# Sheet1_final.net
KiCad netlist of a schematic drawn in Altium Designer
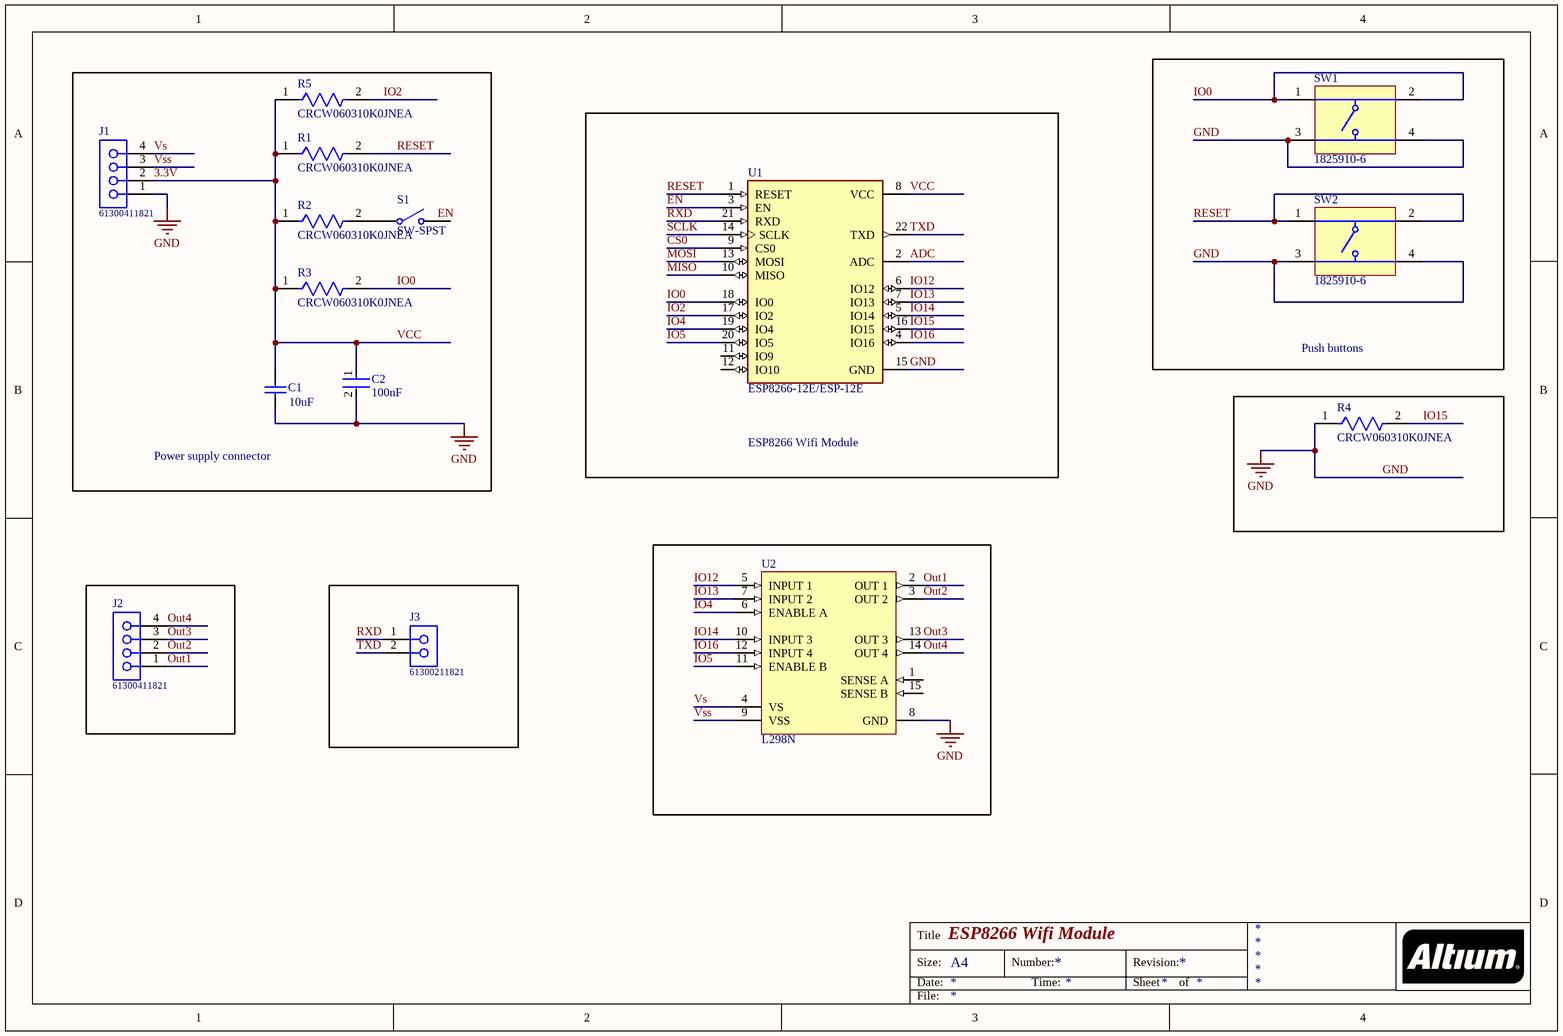
[diagram p0: Sheet1(final).SchDoc]

(export (version "E")
  (design (tool "Eeschema 10.0.6"))
  (components
    (comp (ref "C1")
      (value "10uF")
      (footprint "CAPC2013X95X45ML10T25")
      (fields (field (name "MANUFACTURER") "Murata") (field (name "PART NUMBER") "GRM219R61E106KA12D"))
      (libsource (lib "Altium Content Vault") (part "CAP"))
    )
    (comp (ref "C2")
      (value "100nF")
      (footprint "FP-CL43-IPC_B")
      (description "Cap Ceramic 100nF 500V X7R ±10% SMD 1812 +125°C Embossed T/R")
      (fields (field (name "VOLTAGE") "500V") (field (name "TOLERANCE") "10%"))
      (libsource (lib "Altium Content Vault") (part "b4654b650e69147ec39a6b967a45e02"))
    )
    (comp (ref "J1")
      (value "61300411821")
      (footprint "61300411821")
      (description "WR-PHD Socket Header, THT, pitch 2.54mm, Single Row, Vertical, 4p")
      (fields (field (name "MANUFACTURER") "Wurth Elektronik"))
      (libsource (lib "Altium_WR-PHD (rev20a) (3)") (part "61300411821"))
    )
    (comp (ref "J2")
      (value "61300411821")
      (footprint "61300411821")
      (description "WR-PHD Socket Header, THT, pitch 2.54mm, Single Row, Vertical, 4p")
      (fields (field (name "MANUFACTURER") "Wurth Elektronik"))
      (libsource (lib "Altium_WR-PHD (rev20a) (3)") (part "61300411821"))
    )
    (comp (ref "J3")
      (value "61300211821")
      (footprint "61300211821")
      (description "WR-PHD Socket Header, THT, pitch 2.54mm, Single Row, Vertical, 2p")
      (fields (field (name "MANUFACTURER") "Wurth Elektronik"))
      (libsource (lib "Altium_WR-PHD (rev20a) (3)") (part "61300211821"))
    )
    (comp (ref "R1")
      (value "CRCW060310K0JNEA")
      (footprint "FP-CRCW0603-e3-MFG")
      (description "RES Thick Film, 10kΩ, 5%, 0.1W, 200ppm/°C, 0603")
      (fields (field (name "TOLERANCE") "5%"))
      (libsource (lib "Altium Content Vault") (part "1029c3af85768c4190bb7ad29bc67b5"))
    )
    (comp (ref "R2")
      (value "CRCW060310K0JNEA")
      (footprint "FP-CRCW0603-e3-MFG")
      (description "RES Thick Film, 10kΩ, 5%, 0.1W, 200ppm/°C, 0603")
      (fields (field (name "TOLERANCE") "5%"))
      (libsource (lib "Altium Content Vault") (part "1029c3af85768c4190bb7ad29bc67b5"))
    )
    (comp (ref "R3")
      (value "CRCW060310K0JNEA")
      (footprint "FP-CRCW0603-e3-MFG")
      (description "RES Thick Film, 10kΩ, 5%, 0.1W, 200ppm/°C, 0603")
      (fields (field (name "TOLERANCE") "5%"))
      (libsource (lib "Altium Content Vault") (part "1029c3af85768c4190bb7ad29bc67b5"))
    )
    (comp (ref "R4")
      (value "CRCW060310K0JNEA")
      (footprint "FP-CRCW0603-e3-MFG")
      (description "RES Thick Film, 10kΩ, 5%, 0.1W, 200ppm/°C, 0603")
      (fields (field (name "TOLERANCE") "5%"))
      (libsource (lib "Altium Content Vault") (part "1029c3af85768c4190bb7ad29bc67b5"))
    )
    (comp (ref "R5")
      (value "CRCW060310K0JNEA")
      (footprint "FP-CRCW0603-e3-MFG")
      (description "RES Thick Film, 10kΩ, 5%, 0.1W, 200ppm/°C, 0603")
      (fields (field (name "TOLERANCE") "5%"))
      (libsource (lib "Altium Content Vault") (part "1029c3af85768c4190bb7ad29bc67b5"))
    )
    (comp (ref "S1")
      (value "SW-SPST")
      (footprint "SPST-2")
      (description "Single-Pole, Single-Throw Switch")
      (fields (field (name "PUBLISHER") "Altium Limited"))
      (libsource (lib "Miscellaneous Devices") (part "SW-SPST"))
    )
    (comp (ref "SW1")
      (value "1825910-6")
      (footprint "TECO-1825910-6_V")
      (description "Tact Switch, SPST-NO, 0.05 A, -35 to 85 degC, 4-Pin THD, RoHS, Bulk")
      (fields (field (name "MANUFACTURER") "TE Connectivity"))
      (libsource (lib "Altium Content Vault") (part "SW-SPST-4_A"))
    )
    (comp (ref "SW2")
      (value "1825910-6")
      (footprint "TECO-1825910-6_V")
      (description "Tact Switch, SPST-NO, 0.05 A, -35 to 85 degC, 4-Pin THD, RoHS, Bulk")
      (fields (field (name "MANUFACTURER") "TE Connectivity"))
      (libsource (lib "Altium Content Vault") (part "SW-SPST-4_A"))
    )
    (comp (ref "U1")
      (value "ESP8266-12E/ESP-12E")
      (footprint "XCVR_ESP8266-12E/ESP-12E")
      (fields (field (name "MF") "AI-Thinker"))
      (libsource (lib "ESP8266-12E_ESP-12E") (part "ESP8266-12E/ESP-12E"))
    )
    (comp (ref "U2")
      (value "L298N")
      (footprint "STM-FM-15")
      (description "Dual Full-Bridge Driver, 4.8 to 46 V, -40 to 150 degC, 15-Pin FM (MW 15L), RoHS, Tube")
      (fields (field (name "MANUFACTURER") "STMicroelectronics") (field (name "PARTNUMBER") "L298"))
      (libsource (lib "Altium Content Vault") (part "STM-L298-15"))
    )
  )
  (nets
    (net (code "1") (name "/3.3V") (class "Default")
      (node (ref "C1") (pin "2") (pinfunction "2_2") (pintype "passive"))
      (node (ref "C2") (pin "1") (pinfunction "1_1") (pintype "passive"))
      (node (ref "J1") (pin "2") (pinfunction "2_2") (pintype "passive"))
      (node (ref "R1") (pin "1") (pinfunction "1_1") (pintype "passive"))
      (node (ref "R2") (pin "1") (pinfunction "1_1") (pintype "passive"))
      (node (ref "R3") (pin "1") (pinfunction "1_1") (pintype "passive"))
      (node (ref "R5") (pin "1") (pinfunction "1_1") (pintype "passive"))
      (node (ref "U1") (pin "8") (pinfunction "VCC_8") (pintype "power_in"))
    )
    (net (code "2") (name "/ADC") (class "Default")
      (node (ref "U1") (pin "2") (pinfunction "ADC_2") (pintype "passive"))
    )
    (net (code "3") (name "/CS0") (class "Default")
      (node (ref "U1") (pin "9") (pinfunction "CS0_9") (pintype "input"))
    )
    (net (code "4") (name "/EN") (class "Default")
      (node (ref "U1") (pin "3") (pinfunction "EN_3") (pintype "input"))
    )
    (net (code "5") (name "/IO0") (class "Default")
      (node (ref "R3") (pin "2") (pinfunction "2_2") (pintype "passive"))
      (node (ref "SW1") (pin "1") (pinfunction "1_1") (pintype "passive"))
      (node (ref "SW1") (pin "2") (pinfunction "2_2") (pintype "passive"))
      (node (ref "U1") (pin "18") (pinfunction "IO0_18") (pintype "bidirectional"))
    )
    (net (code "6") (name "/IO2") (class "Default")
      (node (ref "R5") (pin "2") (pinfunction "2_2") (pintype "passive"))
      (node (ref "U1") (pin "17") (pinfunction "IO2_17") (pintype "bidirectional"))
    )
    (net (code "7") (name "/IO4") (class "Default")
      (node (ref "U1") (pin "19") (pinfunction "IO4_19") (pintype "bidirectional"))
      (node (ref "U2") (pin "6") (pinfunction "ENABLE_A_6") (pintype "input"))
    )
    (net (code "8") (name "/IO5") (class "Default")
      (node (ref "U1") (pin "20") (pinfunction "IO5_20") (pintype "bidirectional"))
      (node (ref "U2") (pin "11") (pinfunction "ENABLE_B_11") (pintype "input"))
    )
    (net (code "9") (name "/IO12") (class "Default")
      (node (ref "U1") (pin "6") (pinfunction "IO12_6") (pintype "bidirectional"))
      (node (ref "U2") (pin "5") (pinfunction "INPUT_1_5") (pintype "input"))
    )
    (net (code "10") (name "/IO13") (class "Default")
      (node (ref "U1") (pin "7") (pinfunction "IO13_7") (pintype "bidirectional"))
      (node (ref "U2") (pin "7") (pinfunction "INPUT_2_7") (pintype "input"))
    )
    (net (code "11") (name "/IO14") (class "Default")
      (node (ref "U1") (pin "5") (pinfunction "IO14_5") (pintype "bidirectional"))
      (node (ref "U2") (pin "10") (pinfunction "INPUT_3_10") (pintype "input"))
    )
    (net (code "12") (name "/IO15") (class "Default")
      (node (ref "R4") (pin "2") (pinfunction "2_2") (pintype "passive"))
      (node (ref "U1") (pin "16") (pinfunction "IO15_16") (pintype "bidirectional"))
    )
    (net (code "13") (name "/IO16") (class "Default")
      (node (ref "U1") (pin "4") (pinfunction "IO16_4") (pintype "bidirectional"))
      (node (ref "U2") (pin "12") (pinfunction "INPUT_4_12") (pintype "input"))
    )
    (net (code "14") (name "/MISO") (class "Default")
      (node (ref "U1") (pin "10") (pinfunction "MISO_10") (pintype "bidirectional"))
    )
    (net (code "15") (name "/MOSI") (class "Default")
      (node (ref "U1") (pin "13") (pinfunction "MOSI_13") (pintype "bidirectional"))
    )
    (net (code "16") (name "/Out1") (class "Default")
      (node (ref "J2") (pin "1") (pinfunction "1_1") (pintype "passive"))
      (node (ref "U2") (pin "2") (pinfunction "OUT_1_2") (pintype "output"))
    )
    (net (code "17") (name "/Out2") (class "Default")
      (node (ref "J2") (pin "2") (pinfunction "2_2") (pintype "passive"))
      (node (ref "U2") (pin "3") (pinfunction "OUT_2_3") (pintype "output"))
    )
    (net (code "18") (name "/Out3") (class "Default")
      (node (ref "J2") (pin "3") (pinfunction "3_3") (pintype "passive"))
      (node (ref "U2") (pin "13") (pinfunction "OUT_3_13") (pintype "output"))
    )
    (net (code "19") (name "/Out4") (class "Default")
      (node (ref "J2") (pin "4") (pinfunction "4_4") (pintype "passive"))
      (node (ref "U2") (pin "14") (pinfunction "OUT_4_14") (pintype "output"))
    )
    (net (code "20") (name "/RESET") (class "Default")
      (node (ref "R1") (pin "2") (pinfunction "2_2") (pintype "passive"))
      (node (ref "SW2") (pin "1") (pinfunction "1_1") (pintype "passive"))
      (node (ref "SW2") (pin "2") (pinfunction "2_2") (pintype "passive"))
      (node (ref "U1") (pin "1") (pinfunction "RESET_1") (pintype "input"))
    )
    (net (code "21") (name "/RXD") (class "Default")
      (node (ref "J3") (pin "1") (pinfunction "1_1") (pintype "passive"))
      (node (ref "U1") (pin "21") (pinfunction "RXD_21") (pintype "input"))
    )
    (net (code "22") (name "/SCLK") (class "Default")
      (node (ref "U1") (pin "14") (pinfunction "SCLK_14") (pintype "input"))
    )
    (net (code "23") (name "/TXD") (class "Default")
      (node (ref "J3") (pin "2") (pinfunction "2_2") (pintype "passive"))
      (node (ref "U1") (pin "22") (pinfunction "TXD_22") (pintype "output"))
    )
    (net (code "24") (name "/Vs") (class "Default")
      (node (ref "J1") (pin "4") (pinfunction "4_4") (pintype "passive"))
      (node (ref "U2") (pin "4") (pinfunction "VS_4") (pintype "power_in"))
    )
    (net (code "25") (name "/Vss") (class "Default")
      (node (ref "J1") (pin "3") (pinfunction "3_3") (pintype "passive"))
      (node (ref "U2") (pin "9") (pinfunction "VSS_9") (pintype "power_in"))
    )
    (net (code "26") (name "GND") (class "Default")
      (node (ref "C1") (pin "1") (pinfunction "1_1") (pintype "passive"))
      (node (ref "C2") (pin "2") (pinfunction "2_2") (pintype "passive"))
      (node (ref "J1") (pin "1") (pinfunction "1_1") (pintype "passive"))
      (node (ref "R4") (pin "1") (pinfunction "1_1") (pintype "passive"))
      (node (ref "SW1") (pin "3") (pinfunction "3_3") (pintype "passive"))
      (node (ref "SW1") (pin "4") (pinfunction "4_4") (pintype "passive"))
      (node (ref "SW2") (pin "3") (pinfunction "3_3") (pintype "passive"))
      (node (ref "SW2") (pin "4") (pinfunction "4_4") (pintype "passive"))
      (node (ref "U1") (pin "15") (pinfunction "GND_15") (pintype "power_in"))
      (node (ref "U2") (pin "8") (pinfunction "GND_8") (pintype "power_in"))
    )
    (net (code "27") (name "Net-(S1-COMMON)") (class "Default")
      (node (ref "R2") (pin "2") (pinfunction "2_2") (pintype "passive"))
      (node (ref "S1") (pin "1") (pinfunction "COMMON_1") (pintype "passive"))
    )
    (net (code "28") (name "unconnected-(S1-NO-Pad2)") (class "Default")
      (node (ref "S1") (pin "2") (pinfunction "NO_2") (pintype "passive"))
    )
    (net (code "29") (name "unconnected-(U1-IO9-Pad11)") (class "Default")
      (node (ref "U1") (pin "11") (pinfunction "IO9_11") (pintype "bidirectional"))
    )
    (net (code "30") (name "unconnected-(U1-IO10-Pad12)") (class "Default")
      (node (ref "U1") (pin "12") (pinfunction "IO10_12") (pintype "bidirectional"))
    )
    (net (code "31") (name "unconnected-(U2-SENSE_A-Pad1)") (class "Default")
      (node (ref "U2") (pin "1") (pinfunction "SENSE_A_1") (pintype "input"))
    )
    (net (code "32") (name "unconnected-(U2-SENSE_B-Pad15)") (class "Default")
      (node (ref "U2") (pin "15") (pinfunction "SENSE_B_15") (pintype "input"))
    )
  )
)
